# Controller.net
KiCad netlist of a schematic drawn in Altium Designer
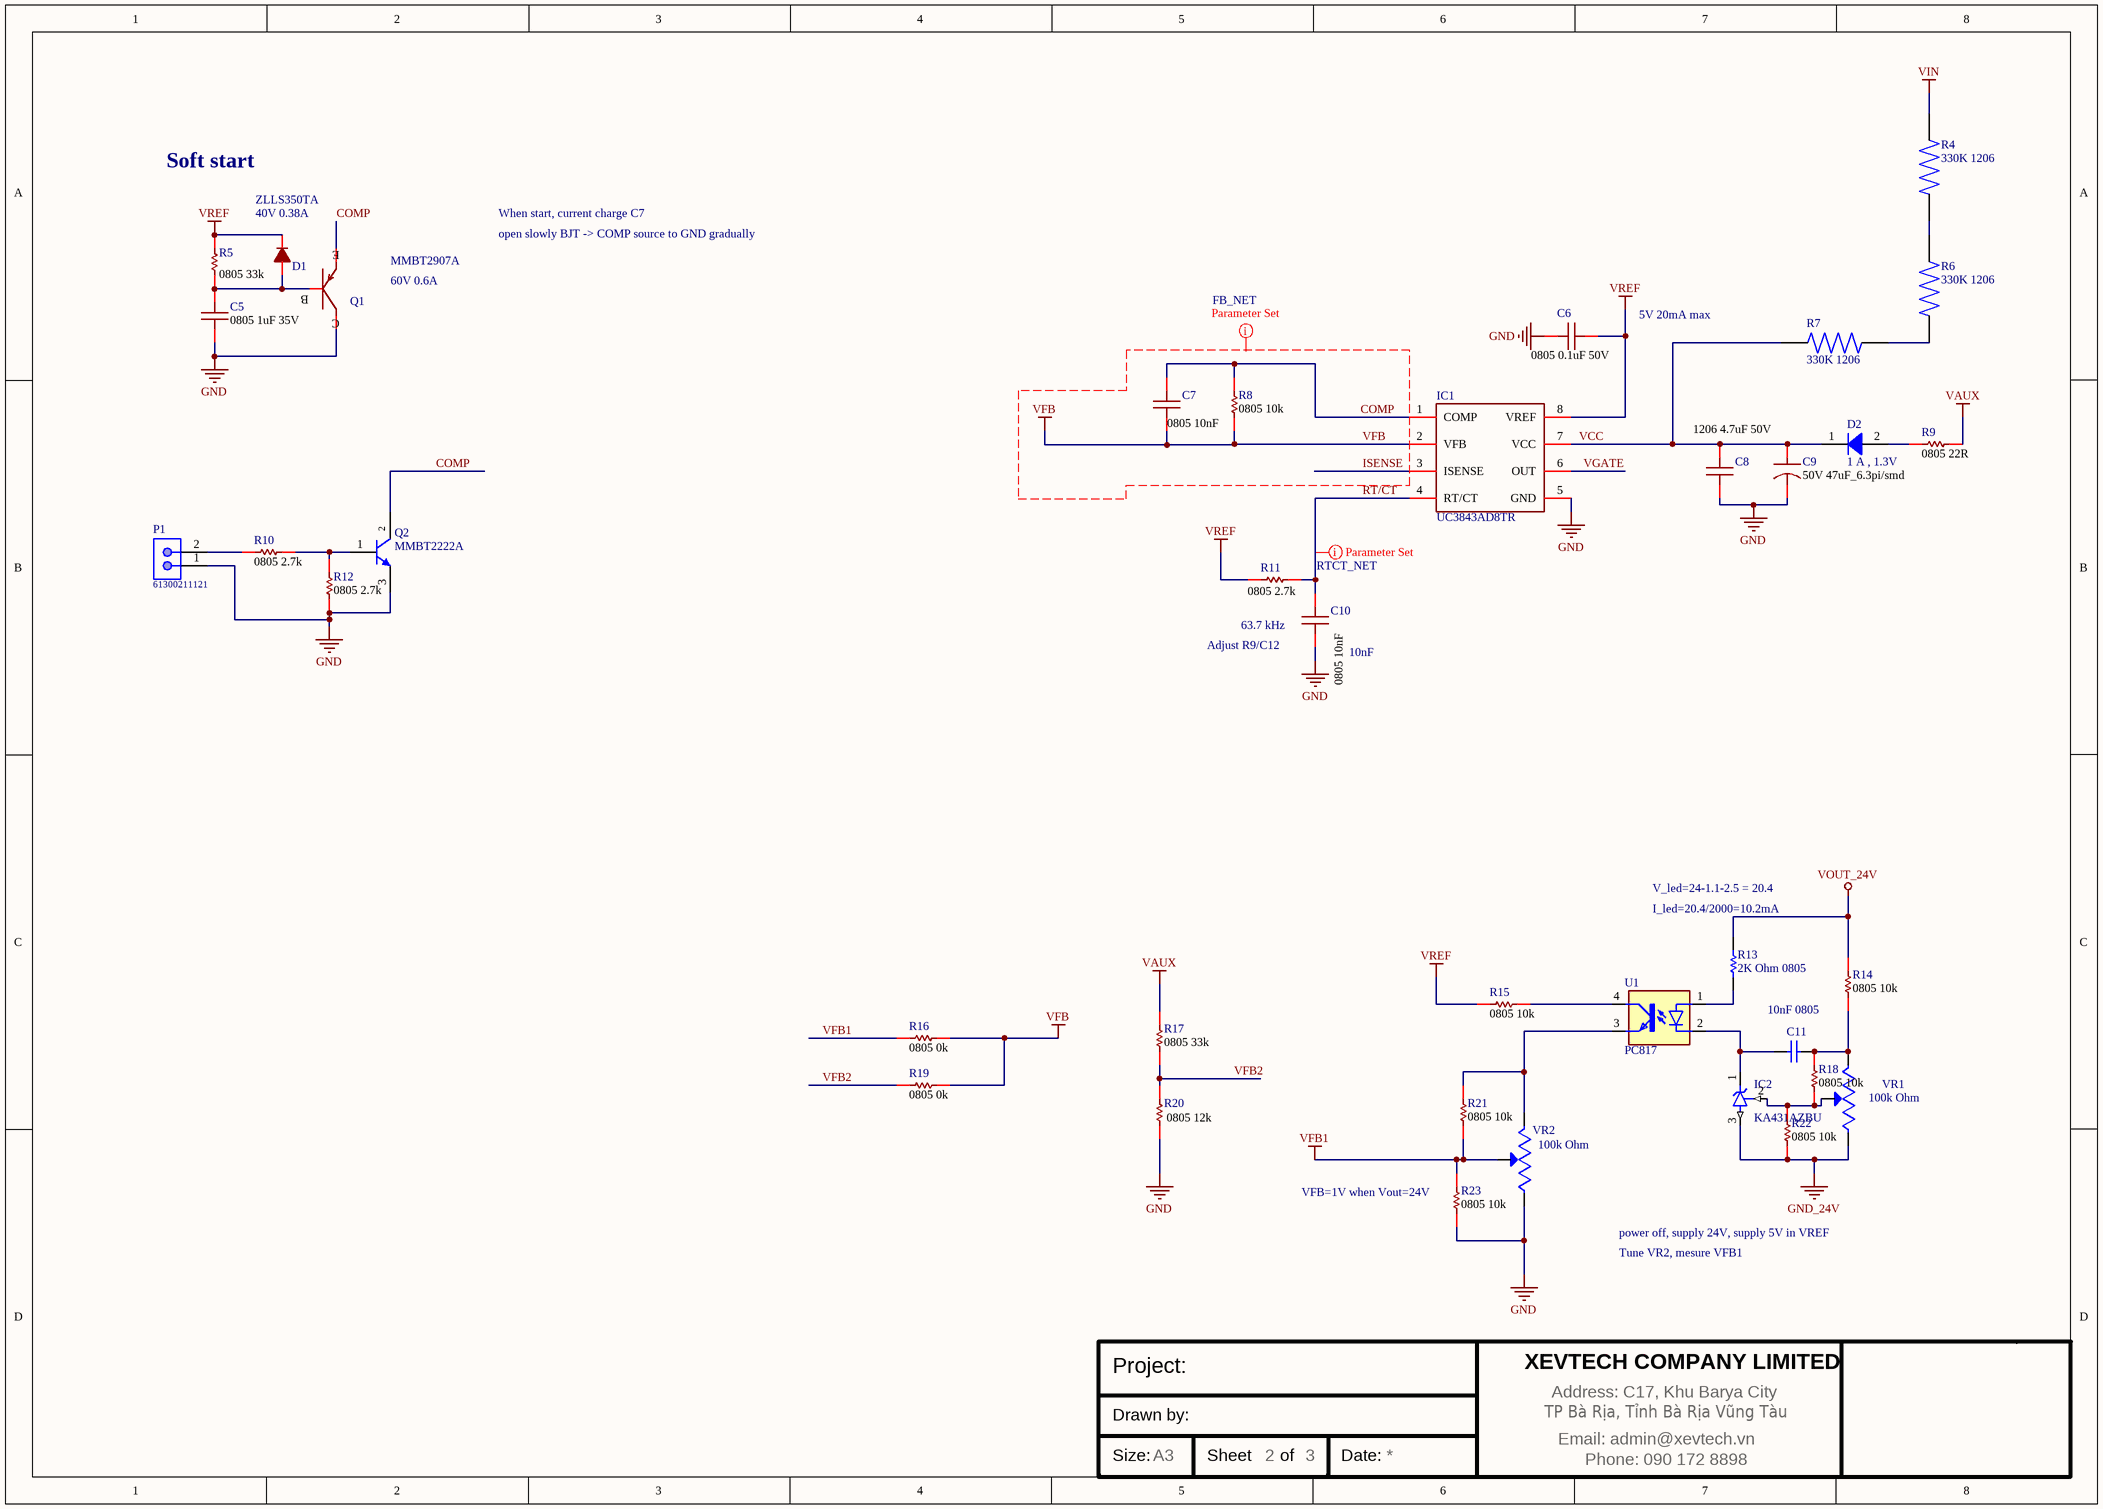
[diagram p0: Controller.SchDoc]

(export (version "E")
  (design (tool "Eeschema 10.0.6"))
  (components
    (comp (ref "C5")
      (value "0805 1uF 35V")
      (footprint "CAP 0805")
      (description "1 µF ±10% 35V Ceramic Capacitor X7R 0805 (2012 Metric)")
      (fields (field (name "Comment") "GRM219R7YA105KA12D"))
      (libsource (lib "xEV_Flyback20W") (part "Cap 0805 1uF"))
    )
    (comp (ref "C6")
      (value "0805 0.1uF 50V")
      (footprint "CAP 0805")
      (description "0.1 µF ±10% 50V Ceramic Capacitor X7R 0805 (2012 Metric)")
      (fields (field (name "Comment") "CL21B104KBCNNNC"))
      (libsource (lib "xEV_Flyback20W") (part "Cap 0805 0.1uF"))
    )
    (comp (ref "C7")
      (value "0805 10nF")
      (footprint "CAP 0805")
      (description "10000 pF ±5% 50V Ceramic Capacitor C0G, NP0 0805 (2012 Metric)")
      (fields (field (name "Comment") "GRM2195C1H103JA01D"))
      (libsource (lib "xEV_Flyback20W") (part "Cap 0805 10nF"))
    )
    (comp (ref "C8")
      (value "1206 4.7uF 50V")
      (footprint "Cap 1206")
      (description "4.7 µF ±20% 50V Ceramic Capacitor X7R 1206 (3216 Metric)")
      (fields (field (name "TOLERANCE") "20%") (field (name "Comment") "C3216X7R1H475M160AC"))
      (libsource (lib "xEV_Flyback20W") (part "Cap 1206 4.7uF"))
    )
    (comp (ref "C9")
      (value "50V 47uF_6.3pi/smd")
      (footprint "C-50-47uf_alu")
      (description "CAP ALUM 47UF 20% 50V SMD")
      (fields (field (name "MANUFACTURER") "Panasonic") (field (name "Comment") "EEE-FK1H470XL"))
      (libsource (lib "xEV_Flyback20W") (part "Capacitor-50V 47u_6.3pi"))
    )
    (comp (ref "C10")
      (value "0805 10nF")
      (footprint "CAP 0805")
      (description "1000 pF 50 VDC 10% 0805 X7R")
      (fields (field (name "Comment") "GCM216R71H102KA37D"))
      (libsource (lib "xEV_Flyback20W") (part "Cap 0805 1nF"))
    )
    (comp (ref "C11")
      (value "10nF 0805")
      (footprint "CAP_0805")
      (description "CAP, size 0805, 8.2 uF, 50 VDC")
      (fields (field (name "TOLERANCE") "+/-5%"))
      (libsource (lib "Altium_Ceramic_Cap") (part "0108058281050"))
    )
    (comp (ref "D1")
      (value "PMEG3010EB,115")
      (footprint "SOD 523")
      (description "Diode 30 V 1A Surface Mount SOD-523")
      (libsource (lib "xEV_Flyback20W") (part "Diode 30V 1A"))
    )
    (comp (ref "D2")
      (value "1 A , 1.3V")
      (footprint "SMA (DO-214AC)")
      (description "Rectifiers 1000V 1a Fast Rect SMa")
      (fields (field (name "MANUFACTURER") "onsemi") (field (name "MANUFACTURER PART NUMBER") "RS1M"))
      (libsource (lib "Altium_Diode") (part "RS1M"))
    )
    (comp (ref "IC1")
      (value "UC3843AD8TR")
      (footprint "UC3843_SOIC8")
      (description "UC3843 Switching IC 8.4V 500kHz")
      (libsource (lib "xEV_Flyback20W") (part "UC3843AD8TR"))
    )
    (comp (ref "IC2")
      (value "KA431AZBU")
      (footprint "SOT23-3")
      (libsource (lib "Mini_Chager_Lib_ALL") (part "KA431AZBU"))
    )
    (comp (ref "P1")
      (value "61300211121")
      (footprint "61300211121")
      (description "WR-PHD Pin Header, THT, pitch 2.54mm, Single Row, Vertical, 2p")
      (fields (field (name "MANUFACTURER") "Wurth Elektronik"))
      (libsource (lib "Altium_Header") (part "61300211121"))
    )
    (comp (ref "Q1")
      (value "MMBT2907A")
      (footprint "SOT 23 3")
      (description "Trans GP BJT PNP 40V 0.2A 300mW Automotive 3-Pin SOT-23 T/R")
      (libsource (lib "xEV_Flyback20W") (part "BJT PNP 40V"))
    )
    (comp (ref "Q2")
      (value "MMBT2222A")
      (footprint "MMBT-SOT23")
      (description "TRANS NPN, 40V, 600MA, SOT23-3")
      (libsource (lib "Altium_BJT") (part "MMBT2222A"))
    )
    (comp (ref "R4")
      (value "330K 1206")
      (footprint "RESC3116X65N")
      (description "13 Ohms Â±5% 0.25W, 1/4W Chip Resistor 1206 (3216 Metric) Moisture Resistant Thick Film")
      (fields (field (name "MP") "RC1206JR-0713RL") (field (name "MF") "Yageo"))
      (libsource (lib "RC1206JR-0713RL (1)") (part "RC1206JR-0713RL"))
    )
    (comp (ref "R5")
      (value "0805 33k")
      (footprint "RES 0805")
      (description "33 kOhms ±1% 0.125W, 1/8W Chip Resistor 0805 (2012 Metric) Moisture Resistant Thick Film")
      (fields (field (name "Comment") "RC0805FR-0733KL"))
      (libsource (lib "xEV_Flyback20W") (part "RES_0805_33k"))
    )
    (comp (ref "R6")
      (value "330K 1206")
      (footprint "RESC3116X65N")
      (description "13 Ohms Â±5% 0.25W, 1/4W Chip Resistor 1206 (3216 Metric) Moisture Resistant Thick Film")
      (fields (field (name "MP") "RC1206JR-0713RL") (field (name "MF") "Yageo"))
      (libsource (lib "RC1206JR-0713RL (1)") (part "RC1206JR-0713RL"))
    )
    (comp (ref "R7")
      (value "330K 1206")
      (footprint "RESC3116X65N")
      (description "13 Ohms Â±5% 0.25W, 1/4W Chip Resistor 1206 (3216 Metric) Moisture Resistant Thick Film")
      (fields (field (name "MP") "RC1206JR-0713RL") (field (name "MF") "Yageo"))
      (libsource (lib "RC1206JR-0713RL (1)") (part "RC1206JR-0713RL"))
    )
    (comp (ref "R8")
      (value "0805 10k")
      (footprint "RES 0805")
      (description "10 kOhms ±1% 0.125W, 1/8W Chip Resistor 0805 (2012 Metric) Moisture Resistant Thick Film")
      (fields (field (name "Comment") "RC0805FR-1310KL"))
      (libsource (lib "xEV_Flyback20W") (part "RES_0805_10k"))
    )
    (comp (ref "R9")
      (value "0805 22R")
      (footprint "RES 0805")
      (fields (field (name "Comment") "RC0805FR-0722RP"))
      (libsource (lib "xEV_Flyback20W") (part "RES_0805_22R"))
    )
    (comp (ref "R10")
      (value "0805 2.7k")
      (footprint "Res 0805")
      (description "12 kOhms ±1% 0.125W, 1/8W Chip Resistor 0805 (2012 Metric) Moisture Resistant Thick Film")
      (fields (field (name "Comment") "RC0805FR-1312KL"))
      (libsource (lib "xEV_Flyback20W") (part "RES_0805_12k"))
    )
    (comp (ref "R11")
      (value "0805 2.7k")
      (footprint "Res 0805")
      (description "12 kOhms ±1% 0.125W, 1/8W Chip Resistor 0805 (2012 Metric) Moisture Resistant Thick Film")
      (fields (field (name "Comment") "RC0805FR-1312KL"))
      (libsource (lib "xEV_Flyback20W") (part "RES_0805_12k"))
    )
    (comp (ref "R12")
      (value "0805 2.7k")
      (footprint "Res 0805")
      (description "12 kOhms ±1% 0.125W, 1/8W Chip Resistor 0805 (2012 Metric) Moisture Resistant Thick Film")
      (fields (field (name "Comment") "RC0805FR-1312KL"))
      (libsource (lib "xEV_Flyback20W") (part "RES_0805_12k"))
    )
    (comp (ref "R13")
      (value "2K Ohm 0805")
      (footprint "RESISTOR_0805")
      (description "RES, size 0805, 4.53 KOhm, 1/8W")
      (libsource (lib "Altium_Resistor") (part "00080545311"))
    )
    (comp (ref "R14")
      (value "0805 10k")
      (footprint "Res 0805")
      (description "100 kOhms ±1% 0.250W, 1/4W Chip Resistor 0805")
      (fields (field (name "Comment") "RK73B2ATTD104J"))
      (libsource (lib "xEV_Flyback20W") (part "RES_0805_100k"))
    )
    (comp (ref "R15")
      (value "0805 10k")
      (footprint "Res 0805")
      (description "100 kOhms ±1% 0.250W, 1/4W Chip Resistor 0805")
      (fields (field (name "Comment") "RK73B2ATTD104J"))
      (libsource (lib "xEV_Flyback20W") (part "RES_0805_100k"))
    )
    (comp (ref "R16")
      (value "0805 0k")
      (footprint "RES 0805")
      (description "10 kOhms ±1% 0.125W, 1/8W Chip Resistor 0805 (2012 Metric) Moisture Resistant Thick Film")
      (fields (field (name "Comment") "RC0805FR-1310KL"))
      (libsource (lib "xEV_Flyback20W") (part "RES_0805_10k"))
    )
    (comp (ref "R17")
      (value "0805 33k")
      (footprint "RES 0805")
      (description "10 kOhms ±1% 0.125W, 1/8W Chip Resistor 0805 (2012 Metric) Moisture Resistant Thick Film")
      (fields (field (name "Comment") "RC0805FR-1310KL"))
      (libsource (lib "xEV_Flyback20W") (part "RES_0805_10k"))
    )
    (comp (ref "R18")
      (value "0805 10k")
      (footprint "Res 0805")
      (description "100 kOhms ±1% 0.250W, 1/4W Chip Resistor 0805")
      (fields (field (name "Comment") "RK73B2ATTD104J"))
      (libsource (lib "xEV_Flyback20W") (part "RES_0805_100k"))
    )
    (comp (ref "R19")
      (value "0805 0k")
      (footprint "RES 0805")
      (description "10 kOhms ±1% 0.125W, 1/8W Chip Resistor 0805 (2012 Metric) Moisture Resistant Thick Film")
      (fields (field (name "Comment") "RC0805FR-1310KL"))
      (libsource (lib "xEV_Flyback20W") (part "RES_0805_10k"))
    )
    (comp (ref "R20")
      (value "0805 12k")
      (footprint "RES 0805")
      (description "10 kOhms ±1% 0.125W, 1/8W Chip Resistor 0805 (2012 Metric) Moisture Resistant Thick Film")
      (fields (field (name "Comment") "RC0805FR-1310KL"))
      (libsource (lib "xEV_Flyback20W") (part "RES_0805_10k"))
    )
    (comp (ref "R21")
      (value "0805 10k")
      (footprint "Res 0805")
      (description "100 kOhms ±1% 0.250W, 1/4W Chip Resistor 0805")
      (fields (field (name "Comment") "RK73B2ATTD104J"))
      (libsource (lib "xEV_Flyback20W") (part "RES_0805_100k"))
    )
    (comp (ref "R22")
      (value "0805 10k")
      (footprint "Res 0805")
      (description "100 kOhms ±1% 0.250W, 1/4W Chip Resistor 0805")
      (fields (field (name "Comment") "RK73B2ATTD104J"))
      (libsource (lib "xEV_Flyback20W") (part "RES_0805_100k"))
    )
    (comp (ref "R23")
      (value "0805 10k")
      (footprint "Res 0805")
      (description "100 kOhms ±1% 0.250W, 1/4W Chip Resistor 0805")
      (fields (field (name "Comment") "RK73B2ATTD104J"))
      (libsource (lib "xEV_Flyback20W") (part "RES_0805_100k"))
    )
    (comp (ref "U1")
      (value "PC817")
      (footprint "PC817")
      (libsource (lib "Mini_Chager_Lib_ALL") (part "PC817"))
    )
    (comp (ref "VR1")
      (value "3296W-1-250")
      (footprint "TRIM_3296W-1-250")
      (description "25 Ohms 0.5W, 1/2W PC Pins Through Hole Trimmer Potentiometer Cermet 25.0 Turn Top Adjustment")
      (fields (field (name "MF") "Bourns"))
      (libsource (lib "Mini_Chager_Lib_ALL") (part "3296W-1-250"))
    )
    (comp (ref "VR2")
      (value "3296W-1-250")
      (footprint "TRIM_3296W-1-250")
      (description "25 Ohms 0.5W, 1/2W PC Pins Through Hole Trimmer Potentiometer Cermet 25.0 Turn Top Adjustment")
      (fields (field (name "MF") "Bourns"))
      (libsource (lib "Mini_Chager_Lib_ALL") (part "3296W-1-250"))
    )
  )
  (nets
    (net (code "1") (name "/COMP") (class "Default")
      (node (ref "C7") (pin "1") (pinfunction "1_1") (pintype "passive"))
      (node (ref "IC1") (pin "1") (pinfunction "COMP_1") (pintype "passive"))
      (node (ref "Q1") (pin "E") (pinfunction "E_E") (pintype "passive"))
      (node (ref "Q2") (pin "2") (pinfunction "C_2") (pintype "passive"))
      (node (ref "R8") (pin "2") (pinfunction "2_2") (pintype "passive"))
    )
    (net (code "2") (name "/ISENSE") (class "Default")
      (node (ref "IC1") (pin "3") (pinfunction "ISENSE_3") (pintype "passive"))
    )
    (net (code "3") (name "/RT{slash}CT") (class "Default")
      (node (ref "C10") (pin "1") (pinfunction "1_1") (pintype "passive"))
      (node (ref "IC1") (pin "4") (pinfunction "RT/CT_4") (pintype "passive"))
      (node (ref "R11") (pin "1") (pinfunction "1_1") (pintype "passive"))
    )
    (net (code "4") (name "/VCC") (class "Default")
      (node (ref "C8") (pin "1") (pinfunction "1_1") (pintype "passive"))
      (node (ref "C9") (pin "1") (pinfunction "1_1") (pintype "passive"))
      (node (ref "D2") (pin "1") (pinfunction "K_1") (pintype "passive"))
      (node (ref "IC1") (pin "7") (pinfunction "VCC_7") (pintype "passive"))
      (node (ref "R7") (pin "2") (pinfunction "2_2") (pintype "passive"))
    )
    (net (code "5") (name "/VFB2") (class "Default")
      (node (ref "R17") (pin "1") (pinfunction "1_1") (pintype "passive"))
      (node (ref "R19") (pin "2") (pinfunction "2_2") (pintype "passive"))
      (node (ref "R20") (pin "2") (pinfunction "2_2") (pintype "passive"))
    )
    (net (code "6") (name "/VGATE") (class "Default")
      (node (ref "IC1") (pin "6") (pinfunction "OUT_6") (pintype "passive"))
    )
    (net (code "7") (name "GND") (class "Default")
      (node (ref "C10") (pin "2") (pinfunction "2_2") (pintype "passive"))
      (node (ref "C5") (pin "2") (pinfunction "2_2") (pintype "passive"))
      (node (ref "C6") (pin "1") (pinfunction "1_1") (pintype "passive"))
      (node (ref "C8") (pin "2") (pinfunction "2_2") (pintype "passive"))
      (node (ref "C9") (pin "2") (pinfunction "2_2") (pintype "passive"))
      (node (ref "IC1") (pin "5") (pinfunction "GND_5") (pintype "passive"))
      (node (ref "P1") (pin "1") (pinfunction "1_1") (pintype "passive"))
      (node (ref "Q1") (pin "C") (pinfunction "C_C") (pintype "passive"))
      (node (ref "Q2") (pin "3") (pinfunction "E_3") (pintype "passive"))
      (node (ref "R12") (pin "2") (pinfunction "2_2") (pintype "passive"))
      (node (ref "R20") (pin "1") (pinfunction "1_1") (pintype "passive"))
      (node (ref "R23") (pin "2") (pinfunction "2_2") (pintype "passive"))
      (node (ref "VR2") (pin "1") (pinfunction "CCW_1") (pintype "passive"))
    )
    (net (code "8") (name "GND_24V") (class "Default")
      (node (ref "IC2") (pin "3") (pinfunction "A_3") (pintype "output"))
      (node (ref "R22") (pin "2") (pinfunction "2_2") (pintype "passive"))
      (node (ref "VR1") (pin "1") (pinfunction "CCW_1") (pintype "passive"))
    )
    (net (code "9") (name "Net-(C5-Pad1)") (class "Default")
      (node (ref "C5") (pin "1") (pinfunction "1_1") (pintype "passive"))
      (node (ref "D1") (pin "A") (pinfunction "A_A") (pintype "passive"))
      (node (ref "Q1") (pin "B") (pinfunction "B_B") (pintype "passive"))
      (node (ref "R5") (pin "2") (pinfunction "2_2") (pintype "passive"))
    )
    (net (code "10") (name "Net-(D2-A)") (class "Default")
      (node (ref "D2") (pin "2") (pinfunction "A_2") (pintype "passive"))
      (node (ref "R9") (pin "2") (pinfunction "2_2") (pintype "passive"))
    )
    (net (code "11") (name "Net-(IC2-C)") (class "Default")
      (node (ref "C11") (pin "2") (pinfunction "2_2") (pintype "passive"))
      (node (ref "IC2") (pin "1") (pinfunction "C_1") (pintype "bidirectional"))
      (node (ref "U1") (pin "2") (pinfunction "C_2") (pintype "passive"))
    )
    (net (code "12") (name "Net-(IC2-REF)") (class "Default")
      (node (ref "IC2") (pin "2") (pinfunction "REF_2") (pintype "input"))
      (node (ref "R18") (pin "2") (pinfunction "2_2") (pintype "passive"))
      (node (ref "R22") (pin "1") (pinfunction "1_1") (pintype "passive"))
      (node (ref "VR1") (pin "2") (pinfunction "WIPER_2") (pintype "passive"))
    )
    (net (code "13") (name "Net-(P1-Pad2)") (class "Default")
      (node (ref "P1") (pin "2") (pinfunction "2_2") (pintype "passive"))
      (node (ref "R10") (pin "1") (pinfunction "1_1") (pintype "passive"))
    )
    (net (code "14") (name "Net-(Q2-B)") (class "Default")
      (node (ref "Q2") (pin "1") (pinfunction "B_1") (pintype "passive"))
      (node (ref "R10") (pin "2") (pinfunction "2_2") (pintype "passive"))
      (node (ref "R12") (pin "1") (pinfunction "1_1") (pintype "passive"))
    )
    (net (code "15") (name "Net-(R4-Pad1)") (class "Default")
      (node (ref "R4") (pin "1") (pinfunction "1_1") (pintype "passive"))
      (node (ref "R6") (pin "2") (pinfunction "2_2") (pintype "passive"))
    )
    (net (code "16") (name "Net-(R6-Pad1)") (class "Default")
      (node (ref "R6") (pin "1") (pinfunction "1_1") (pintype "passive"))
      (node (ref "R7") (pin "1") (pinfunction "1_1") (pintype "passive"))
    )
    (net (code "17") (name "Net-(U1-A)") (class "Default")
      (node (ref "R13") (pin "1") (pinfunction "1_1") (pintype "passive"))
      (node (ref "U1") (pin "1") (pinfunction "A_1") (pintype "passive"))
    )
    (net (code "18") (name "Net-(U1-COL)") (class "Default")
      (node (ref "R15") (pin "1") (pinfunction "1_1") (pintype "passive"))
      (node (ref "U1") (pin "4") (pinfunction "COL_4") (pintype "passive"))
    )
    (net (code "19") (name "Net-(U1-EMIT)") (class "Default")
      (node (ref "R21") (pin "1") (pinfunction "1_1") (pintype "passive"))
      (node (ref "U1") (pin "3") (pinfunction "EMIT_3") (pintype "passive"))
      (node (ref "VR2") (pin "3") (pinfunction "CW_3") (pintype "passive"))
    )
    (net (code "20") (name "Net-(VR1-CW)") (class "Default")
      (node (ref "C11") (pin "1") (pinfunction "1_1") (pintype "passive"))
      (node (ref "R14") (pin "1") (pinfunction "1_1") (pintype "passive"))
      (node (ref "R18") (pin "1") (pinfunction "1_1") (pintype "passive"))
      (node (ref "VR1") (pin "3") (pinfunction "CW_3") (pintype "passive"))
    )
    (net (code "21") (name "VAUX") (class "Default")
      (node (ref "R17") (pin "2") (pinfunction "2_2") (pintype "passive"))
      (node (ref "R9") (pin "1") (pinfunction "1_1") (pintype "passive"))
    )
    (net (code "22") (name "VFB") (class "Default")
      (node (ref "C7") (pin "2") (pinfunction "2_2") (pintype "passive"))
      (node (ref "IC1") (pin "2") (pinfunction "VFB_2") (pintype "passive"))
      (node (ref "R16") (pin "1") (pinfunction "1_1") (pintype "passive"))
      (node (ref "R19") (pin "1") (pinfunction "1_1") (pintype "passive"))
      (node (ref "R8") (pin "1") (pinfunction "1_1") (pintype "passive"))
    )
    (net (code "23") (name "VFB1") (class "Default")
      (node (ref "R16") (pin "2") (pinfunction "2_2") (pintype "passive"))
      (node (ref "R21") (pin "2") (pinfunction "2_2") (pintype "passive"))
      (node (ref "R23") (pin "1") (pinfunction "1_1") (pintype "passive"))
      (node (ref "VR2") (pin "2") (pinfunction "WIPER_2") (pintype "passive"))
    )
    (net (code "24") (name "VIN") (class "Default")
      (node (ref "R4") (pin "2") (pinfunction "2_2") (pintype "passive"))
    )
    (net (code "25") (name "VOUT_24V") (class "Default")
      (node (ref "R13") (pin "2") (pinfunction "2_2") (pintype "passive"))
      (node (ref "R14") (pin "2") (pinfunction "2_2") (pintype "passive"))
    )
    (net (code "26") (name "VREF") (class "Default")
      (node (ref "C6") (pin "2") (pinfunction "2_2") (pintype "passive"))
      (node (ref "D1") (pin "K") (pinfunction "K_K") (pintype "passive"))
      (node (ref "IC1") (pin "8") (pinfunction "VREF_8") (pintype "passive"))
      (node (ref "R11") (pin "2") (pinfunction "2_2") (pintype "passive"))
      (node (ref "R15") (pin "2") (pinfunction "2_2") (pintype "passive"))
      (node (ref "R5") (pin "1") (pinfunction "1_1") (pintype "passive"))
    )
  )
)
